# Sheet1.net
KiCad netlist of a schematic drawn in Altium Designer
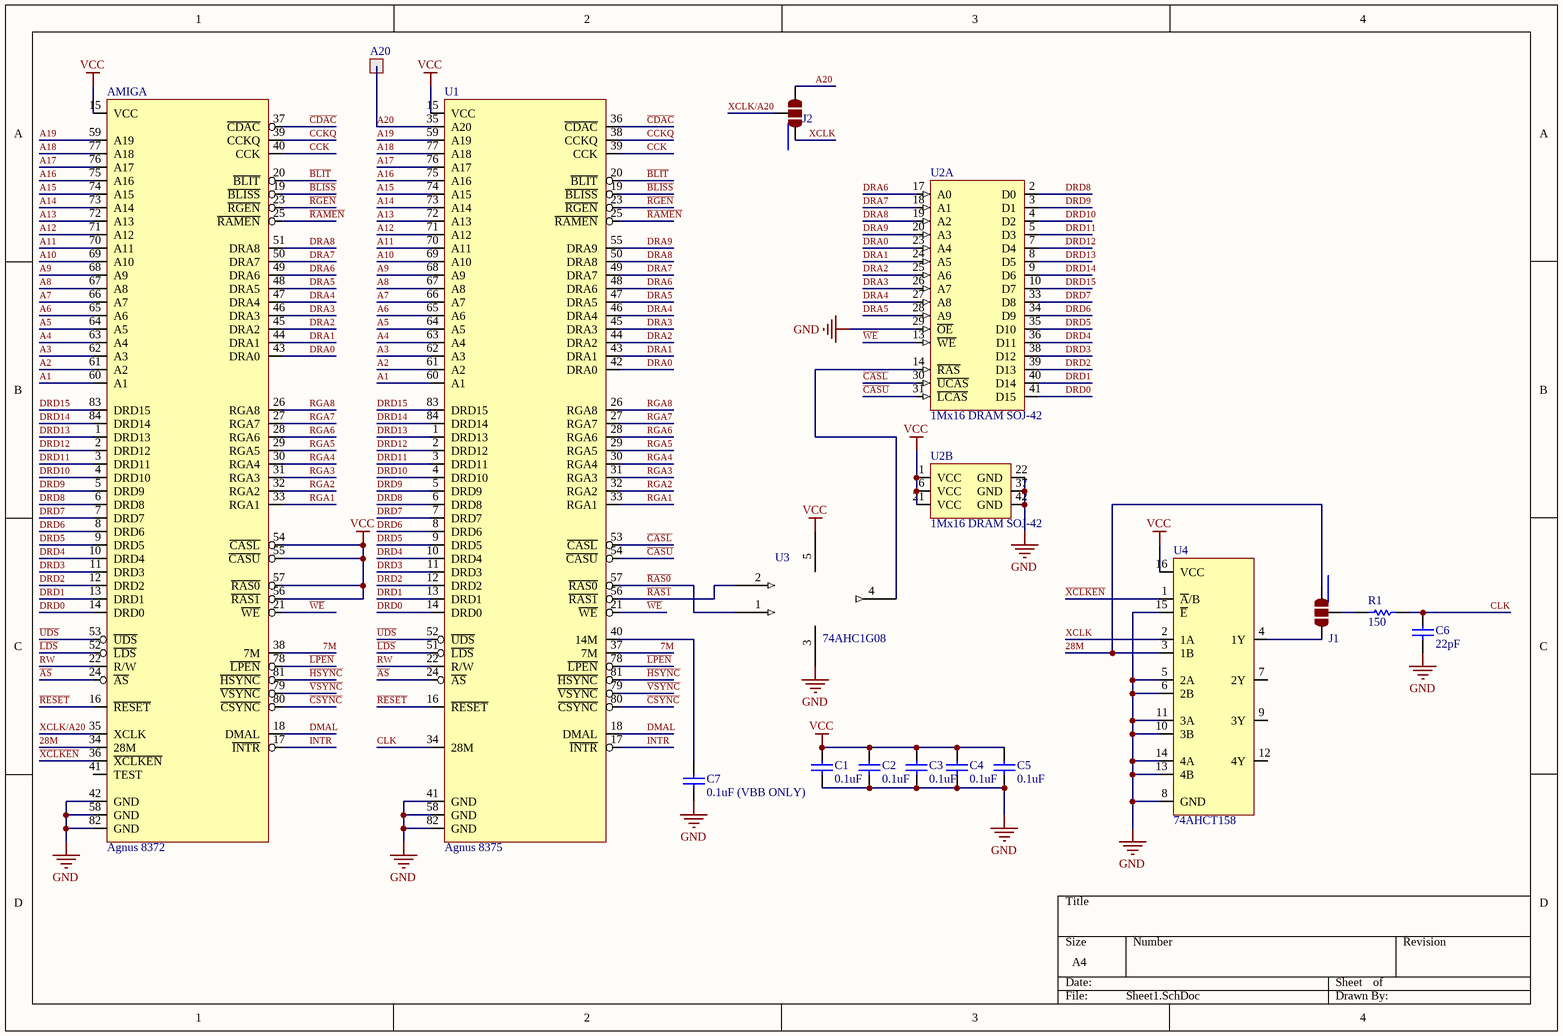
[diagram p0: Sheet1.SchDoc]

(export (version "E")
  (design (tool "Eeschema 10.0.6"))
  (components
    (comp (ref "A20")
      (value "Molex 90120-0761")
      (footprint "PCB-u1j2a009byds4mriae4x-1")
      (description "2.54mm (.100\") Pitch C-Grid III Header, Single Row, Vertical, 40 Circuits, Gold (Au) Plating")
      (fields (field (name "MANUFACTURER PART NUMBER") "90120-0761"))
      (libsource (lib "CommunityVault") (part "CMP-b48f7df16db76b48-3"))
    )
    (comp (ref "AMIGA")
      (value "Agnus 8372")
      (footprint "PLCC Male plug")
      (description "1MB Agnus (A500/2000)")
      (libsource (lib "CommunityVault") (part "CMP-efwu862vrdu0d84ikc4y-6"))
    )
    (comp (ref "C1")
      (value "0.1uF")
      (footprint "CAPC2013X94X50NL20T25")
      (description "CAP CER 0.1UF 25V Y5V 0805")
      (fields (field (name "MANUFACTURER PART NUMBER") "08053G104ZAT2A"))
      (libsource (lib "CommunityVault") (part "CMP-126070-2"))
    )
    (comp (ref "C2")
      (value "0.1uF")
      (footprint "CAPC2013X94X50NL20T25")
      (description "CAP CER 0.1UF 25V Y5V 0805")
      (fields (field (name "MANUFACTURER PART NUMBER") "08053G104ZAT2A"))
      (libsource (lib "CommunityVault") (part "CMP-126070-2"))
    )
    (comp (ref "C3")
      (value "0.1uF")
      (footprint "CAPC2013X94X50NL20T25")
      (description "CAP CER 0.1UF 25V Y5V 0805")
      (fields (field (name "MANUFACTURER PART NUMBER") "08053G104ZAT2A"))
      (libsource (lib "CommunityVault") (part "CMP-126070-2"))
    )
    (comp (ref "C4")
      (value "0.1uF")
      (footprint "CAPC2013X94X50NL20T25")
      (description "CAP CER 0.1UF 25V Y5V 0805")
      (fields (field (name "MANUFACTURER PART NUMBER") "08053G104ZAT2A"))
      (libsource (lib "CommunityVault") (part "CMP-126070-2"))
    )
    (comp (ref "C5")
      (value "0.1uF")
      (footprint "CAPC2013X94X50NL20T25")
      (description "CAP CER 0.1UF 25V Y5V 0805")
      (fields (field (name "MANUFACTURER PART NUMBER") "08053G104ZAT2A"))
      (libsource (lib "CommunityVault") (part "CMP-126070-2"))
    )
    (comp (ref "C6")
      (value "22pF")
      (footprint "CAPC2013X140X50NL20T25")
      (description "CAP CER 22PF 100V 5% NP0 0805")
      (fields (field (name "MANUFACTURER PART NUMBER") "08051A220J4T2A"))
      (libsource (lib "CommunityVault") (part "CMP-172484-2"))
    )
    (comp (ref "C7")
      (value "0.1uF (VBB ONLY)")
      (footprint "CAPC2013X94X50NL20T25")
      (description "CAP CER 0.1UF 25V Y5V 0805")
      (fields (field (name "MANUFACTURER PART NUMBER") "08053G104ZAT2A"))
      (libsource (lib "CommunityVault") (part "CMP-126070-2"))
    )
    (comp (ref "J1")
      (value "H1")
      (footprint "PCB-rrnqmtokqinrd1vbp5jt-1")
      (description "SMD Jumper")
      (libsource (lib "FavoritesLibrary") (part "SYM-0rfjo47dqw9gp5mzow1m-1"))
    )
    (comp (ref "J2")
      (value "H1")
      (footprint "PCB-rrnqmtokqinrd1vbp5jt-1")
      (description "SMD Jumper")
      (libsource (lib "CommunityVault") (part "CMP-0rfjo47dqw9gp5mzow1m-3"))
    )
    (comp (ref "R1")
      (value "150")
      (footprint "RESC2013X60X30NL20T20")
      (description "Res Thick Film 0805 150 Ohm 1% 1/8W ±100ppm/C Molded SMD SMD Punched Paper T/R")
      (fields (field (name "MANUFACTURER PART NUMBER") "RK73H2ATTD1500F"))
      (libsource (lib "CommunityVault") (part "CMP-2823328-2"))
    )
    (comp (ref "U1")
      (value "Agnus 8375")
      (footprint "PCBComponent_1")
      (description "2MB Agnus (A500+/A600)")
      (libsource (lib "CommunityVault") (part "CMP-7khi6ttu66jii6hcxoo5-4"))
    )
    (comp (ref "U2")
      (value "1Mx16 DRAM SOJ-42")
      (footprint "SOP42")
      (description "Generic 5V 16Mbit EDO DRAM SOJ42")
      (libsource (lib "CommunityVault") (part "CMP-upz9ayrn6n7gqqnzejzn-3"))
    )
    (comp (ref "U3")
      (value "74AHC1G08")
      (footprint "PCB-hs9ieo8jn20xo1glw5j0-1")
      (description "Logic, And Gate, Single, 2 i/p, Tssop-5")
      (libsource (lib "FavoritesLibrary") (part "SYM-eb1b2368527234dc-1"))
    )
    (comp (ref "U4")
      (value "74AHCT158")
      (footprint "PCB-c1qa6rkk0qsamo5yebiy-1")
      (description "74AHC Series 2 to 5.5 V Quad 2-Input Multiplexer Surface Mount - SOIC-16")
      (fields (field (name "MANUFACTURER PART NUMBER") "74AHC157D,112"))
      (libsource (lib "CommunityVault") (part "CMP-483e8585f23297f9-2"))
    )
  )
  (nets
    (net (code "1") (name "/7M") (class "Default")
      (node (ref "AMIGA") (pin "38") (pinfunction "7M_38") (pintype "passive"))
      (node (ref "U1") (pin "37") (pinfunction "7M_37") (pintype "passive"))
    )
    (net (code "2") (name "/28M") (class "Default")
      (node (ref "AMIGA") (pin "34") (pinfunction "28M_34") (pintype "passive"))
      (node (ref "J1") (pin "1") (pinfunction "1_1") (pintype "passive"))
      (node (ref "U4") (pin "3") (pinfunction "1B_3") (pintype "passive"))
    )
    (net (code "3") (name "/A1") (class "Default")
      (node (ref "AMIGA") (pin "60") (pinfunction "A1_60") (pintype "passive"))
      (node (ref "U1") (pin "60") (pinfunction "A1_60") (pintype "passive"))
    )
    (net (code "4") (name "/A2") (class "Default")
      (node (ref "AMIGA") (pin "61") (pinfunction "A2_61") (pintype "passive"))
      (node (ref "U1") (pin "61") (pinfunction "A2_61") (pintype "passive"))
    )
    (net (code "5") (name "/A3") (class "Default")
      (node (ref "AMIGA") (pin "62") (pinfunction "A3_62") (pintype "passive"))
      (node (ref "U1") (pin "62") (pinfunction "A3_62") (pintype "passive"))
    )
    (net (code "6") (name "/A4") (class "Default")
      (node (ref "AMIGA") (pin "63") (pinfunction "A4_63") (pintype "passive"))
      (node (ref "U1") (pin "63") (pinfunction "A4_63") (pintype "passive"))
    )
    (net (code "7") (name "/A5") (class "Default")
      (node (ref "AMIGA") (pin "64") (pinfunction "A5_64") (pintype "passive"))
      (node (ref "U1") (pin "64") (pinfunction "A5_64") (pintype "passive"))
    )
    (net (code "8") (name "/A6") (class "Default")
      (node (ref "AMIGA") (pin "65") (pinfunction "A6_65") (pintype "passive"))
      (node (ref "U1") (pin "65") (pinfunction "A6_65") (pintype "passive"))
    )
    (net (code "9") (name "/A7") (class "Default")
      (node (ref "AMIGA") (pin "66") (pinfunction "A7_66") (pintype "passive"))
      (node (ref "U1") (pin "66") (pinfunction "A7_66") (pintype "passive"))
    )
    (net (code "10") (name "/A8") (class "Default")
      (node (ref "AMIGA") (pin "67") (pinfunction "A8_67") (pintype "passive"))
      (node (ref "U1") (pin "67") (pinfunction "A8_67") (pintype "passive"))
    )
    (net (code "11") (name "/A9") (class "Default")
      (node (ref "AMIGA") (pin "68") (pinfunction "A9_68") (pintype "passive"))
      (node (ref "U1") (pin "68") (pinfunction "A9_68") (pintype "passive"))
    )
    (net (code "12") (name "/A10") (class "Default")
      (node (ref "AMIGA") (pin "69") (pinfunction "A10_69") (pintype "passive"))
      (node (ref "U1") (pin "69") (pinfunction "A10_69") (pintype "passive"))
    )
    (net (code "13") (name "/A11") (class "Default")
      (node (ref "AMIGA") (pin "70") (pinfunction "A11_70") (pintype "passive"))
      (node (ref "U1") (pin "70") (pinfunction "A11_70") (pintype "passive"))
    )
    (net (code "14") (name "/A12") (class "Default")
      (node (ref "AMIGA") (pin "71") (pinfunction "A12_71") (pintype "passive"))
      (node (ref "U1") (pin "71") (pinfunction "A12_71") (pintype "passive"))
    )
    (net (code "15") (name "/A13") (class "Default")
      (node (ref "AMIGA") (pin "72") (pinfunction "A13_72") (pintype "passive"))
      (node (ref "U1") (pin "72") (pinfunction "A13_72") (pintype "passive"))
    )
    (net (code "16") (name "/A14") (class "Default")
      (node (ref "AMIGA") (pin "73") (pinfunction "A14_73") (pintype "passive"))
      (node (ref "U1") (pin "73") (pinfunction "A14_73") (pintype "passive"))
    )
    (net (code "17") (name "/A15") (class "Default")
      (node (ref "AMIGA") (pin "74") (pinfunction "A15_74") (pintype "passive"))
      (node (ref "U1") (pin "74") (pinfunction "A15_74") (pintype "passive"))
    )
    (net (code "18") (name "/A16") (class "Default")
      (node (ref "AMIGA") (pin "75") (pinfunction "A16_75") (pintype "passive"))
      (node (ref "U1") (pin "75") (pinfunction "A16_75") (pintype "passive"))
    )
    (net (code "19") (name "/A17") (class "Default")
      (node (ref "AMIGA") (pin "76") (pinfunction "A17_76") (pintype "passive"))
      (node (ref "U1") (pin "76") (pinfunction "A17_76") (pintype "passive"))
    )
    (net (code "20") (name "/A18") (class "Default")
      (node (ref "AMIGA") (pin "77") (pinfunction "A18_77") (pintype "passive"))
      (node (ref "U1") (pin "77") (pinfunction "A18_77") (pintype "passive"))
    )
    (net (code "21") (name "/A19") (class "Default")
      (node (ref "AMIGA") (pin "59") (pinfunction "A19_59") (pintype "passive"))
      (node (ref "U1") (pin "59") (pinfunction "A19_59") (pintype "passive"))
    )
    (net (code "22") (name "/A20") (class "Default")
      (node (ref "A20") (pin "1") (pinfunction "1_1") (pintype "passive"))
      (node (ref "J2") (pin "3") (pinfunction "3_3") (pintype "passive"))
      (node (ref "U1") (pin "35") (pinfunction "A20_35") (pintype "passive"))
    )
    (net (code "23") (name "/CCK") (class "Default")
      (node (ref "AMIGA") (pin "40") (pinfunction "CCK_40") (pintype "passive"))
      (node (ref "U1") (pin "39") (pinfunction "CCK_39") (pintype "passive"))
    )
    (net (code "24") (name "/CCKQ") (class "Default")
      (node (ref "AMIGA") (pin "39") (pinfunction "CCKQ_39") (pintype "passive"))
      (node (ref "U1") (pin "38") (pinfunction "CCKQ_38") (pintype "passive"))
    )
    (net (code "25") (name "/CLK") (class "Default")
      (node (ref "C6") (pin "2") (pinfunction "2_2") (pintype "passive"))
      (node (ref "R1") (pin "2") (pinfunction "2_2") (pintype "passive"))
      (node (ref "U1") (pin "34") (pinfunction "28M_34") (pintype "passive"))
    )
    (net (code "26") (name "/DMAL") (class "Default")
      (node (ref "AMIGA") (pin "18") (pinfunction "DMAL_18") (pintype "passive"))
      (node (ref "U1") (pin "18") (pinfunction "DMAL_18") (pintype "passive"))
    )
    (net (code "27") (name "/DRA0") (class "Default")
      (node (ref "AMIGA") (pin "43") (pinfunction "DRA0_43") (pintype "passive"))
      (node (ref "U1") (pin "42") (pinfunction "DRA0_42") (pintype "passive"))
      (node (ref "U2") (pin "23") (pinfunction "A4_23") (pintype "input"))
    )
    (net (code "28") (name "/DRA1") (class "Default")
      (node (ref "AMIGA") (pin "44") (pinfunction "DRA1_44") (pintype "passive"))
      (node (ref "U1") (pin "43") (pinfunction "DRA1_43") (pintype "passive"))
      (node (ref "U2") (pin "24") (pinfunction "A5_24") (pintype "input"))
    )
    (net (code "29") (name "/DRA2") (class "Default")
      (node (ref "AMIGA") (pin "45") (pinfunction "DRA2_45") (pintype "passive"))
      (node (ref "U1") (pin "44") (pinfunction "DRA2_44") (pintype "passive"))
      (node (ref "U2") (pin "25") (pinfunction "A6_25") (pintype "input"))
    )
    (net (code "30") (name "/DRA3") (class "Default")
      (node (ref "AMIGA") (pin "46") (pinfunction "DRA3_46") (pintype "passive"))
      (node (ref "U1") (pin "45") (pinfunction "DRA3_45") (pintype "passive"))
      (node (ref "U2") (pin "26") (pinfunction "A7_26") (pintype "input"))
    )
    (net (code "31") (name "/DRA4") (class "Default")
      (node (ref "AMIGA") (pin "47") (pinfunction "DRA4_47") (pintype "passive"))
      (node (ref "U1") (pin "46") (pinfunction "DRA4_46") (pintype "passive"))
      (node (ref "U2") (pin "27") (pinfunction "A8_27") (pintype "input"))
    )
    (net (code "32") (name "/DRA5") (class "Default")
      (node (ref "AMIGA") (pin "48") (pinfunction "DRA5_48") (pintype "passive"))
      (node (ref "U1") (pin "47") (pinfunction "DRA5_47") (pintype "passive"))
      (node (ref "U2") (pin "28") (pinfunction "A9_28") (pintype "input"))
    )
    (net (code "33") (name "/DRA6") (class "Default")
      (node (ref "AMIGA") (pin "49") (pinfunction "DRA6_49") (pintype "passive"))
      (node (ref "U1") (pin "48") (pinfunction "DRA6_48") (pintype "passive"))
      (node (ref "U2") (pin "17") (pinfunction "A0_17") (pintype "input"))
    )
    (net (code "34") (name "/DRA7") (class "Default")
      (node (ref "AMIGA") (pin "50") (pinfunction "DRA7_50") (pintype "passive"))
      (node (ref "U1") (pin "49") (pinfunction "DRA7_49") (pintype "passive"))
      (node (ref "U2") (pin "18") (pinfunction "A1_18") (pintype "input"))
    )
    (net (code "35") (name "/DRA8") (class "Default")
      (node (ref "AMIGA") (pin "51") (pinfunction "DRA8_51") (pintype "passive"))
      (node (ref "U1") (pin "50") (pinfunction "DRA8_50") (pintype "passive"))
      (node (ref "U2") (pin "19") (pinfunction "A2_19") (pintype "input"))
    )
    (net (code "36") (name "/DRA9") (class "Default")
      (node (ref "U1") (pin "55") (pinfunction "DRA9_55") (pintype "passive"))
      (node (ref "U2") (pin "20") (pinfunction "A3_20") (pintype "input"))
    )
    (net (code "37") (name "/DRD0") (class "Default")
      (node (ref "AMIGA") (pin "14") (pinfunction "DRD0_14") (pintype "passive"))
      (node (ref "U1") (pin "14") (pinfunction "DRD0_14") (pintype "passive"))
      (node (ref "U2") (pin "41") (pinfunction "D15_41") (pintype "bidirectional"))
    )
    (net (code "38") (name "/DRD1") (class "Default")
      (node (ref "AMIGA") (pin "13") (pinfunction "DRD1_13") (pintype "passive"))
      (node (ref "U1") (pin "13") (pinfunction "DRD1_13") (pintype "passive"))
      (node (ref "U2") (pin "40") (pinfunction "D14_40") (pintype "bidirectional"))
    )
    (net (code "39") (name "/DRD2") (class "Default")
      (node (ref "AMIGA") (pin "12") (pinfunction "DRD2_12") (pintype "passive"))
      (node (ref "U1") (pin "12") (pinfunction "DRD2_12") (pintype "passive"))
      (node (ref "U2") (pin "39") (pinfunction "D13_39") (pintype "bidirectional"))
    )
    (net (code "40") (name "/DRD3") (class "Default")
      (node (ref "AMIGA") (pin "11") (pinfunction "DRD3_11") (pintype "passive"))
      (node (ref "U1") (pin "11") (pinfunction "DRD3_11") (pintype "passive"))
      (node (ref "U2") (pin "38") (pinfunction "D12_38") (pintype "bidirectional"))
    )
    (net (code "41") (name "/DRD4") (class "Default")
      (node (ref "AMIGA") (pin "10") (pinfunction "DRD4_10") (pintype "passive"))
      (node (ref "U1") (pin "10") (pinfunction "DRD4_10") (pintype "passive"))
      (node (ref "U2") (pin "36") (pinfunction "D11_36") (pintype "bidirectional"))
    )
    (net (code "42") (name "/DRD5") (class "Default")
      (node (ref "AMIGA") (pin "9") (pinfunction "DRD5_9") (pintype "passive"))
      (node (ref "U1") (pin "9") (pinfunction "DRD5_9") (pintype "passive"))
      (node (ref "U2") (pin "35") (pinfunction "D10_35") (pintype "bidirectional"))
    )
    (net (code "43") (name "/DRD6") (class "Default")
      (node (ref "AMIGA") (pin "8") (pinfunction "DRD6_8") (pintype "passive"))
      (node (ref "U1") (pin "8") (pinfunction "DRD6_8") (pintype "passive"))
      (node (ref "U2") (pin "34") (pinfunction "D9_34") (pintype "bidirectional"))
    )
    (net (code "44") (name "/DRD7") (class "Default")
      (node (ref "AMIGA") (pin "7") (pinfunction "DRD7_7") (pintype "passive"))
      (node (ref "U1") (pin "7") (pinfunction "DRD7_7") (pintype "passive"))
      (node (ref "U2") (pin "33") (pinfunction "D8_33") (pintype "bidirectional"))
    )
    (net (code "45") (name "/DRD8") (class "Default")
      (node (ref "AMIGA") (pin "6") (pinfunction "DRD8_6") (pintype "passive"))
      (node (ref "U1") (pin "6") (pinfunction "DRD8_6") (pintype "passive"))
      (node (ref "U2") (pin "2") (pinfunction "D0_2") (pintype "bidirectional"))
    )
    (net (code "46") (name "/DRD9") (class "Default")
      (node (ref "AMIGA") (pin "5") (pinfunction "DRD9_5") (pintype "passive"))
      (node (ref "U1") (pin "5") (pinfunction "DRD9_5") (pintype "passive"))
      (node (ref "U2") (pin "3") (pinfunction "D1_3") (pintype "bidirectional"))
    )
    (net (code "47") (name "/DRD10") (class "Default")
      (node (ref "AMIGA") (pin "4") (pinfunction "DRD10_4") (pintype "passive"))
      (node (ref "U1") (pin "4") (pinfunction "DRD10_4") (pintype "passive"))
      (node (ref "U2") (pin "4") (pinfunction "D2_4") (pintype "bidirectional"))
    )
    (net (code "48") (name "/DRD11") (class "Default")
      (node (ref "AMIGA") (pin "3") (pinfunction "DRD11_3") (pintype "passive"))
      (node (ref "U1") (pin "3") (pinfunction "DRD11_3") (pintype "passive"))
      (node (ref "U2") (pin "5") (pinfunction "D3_5") (pintype "bidirectional"))
    )
    (net (code "49") (name "/DRD12") (class "Default")
      (node (ref "AMIGA") (pin "2") (pinfunction "DRD12_2") (pintype "passive"))
      (node (ref "U1") (pin "2") (pinfunction "DRD12_2") (pintype "passive"))
      (node (ref "U2") (pin "7") (pinfunction "D4_7") (pintype "bidirectional"))
    )
    (net (code "50") (name "/DRD13") (class "Default")
      (node (ref "AMIGA") (pin "1") (pinfunction "DRD13_1") (pintype "passive"))
      (node (ref "U1") (pin "1") (pinfunction "DRD13_1") (pintype "passive"))
      (node (ref "U2") (pin "8") (pinfunction "D5_8") (pintype "bidirectional"))
    )
    (net (code "51") (name "/DRD14") (class "Default")
      (node (ref "AMIGA") (pin "84") (pinfunction "DRD14_84") (pintype "passive"))
      (node (ref "U1") (pin "84") (pinfunction "DRD14_84") (pintype "passive"))
      (node (ref "U2") (pin "9") (pinfunction "D6_9") (pintype "bidirectional"))
    )
    (net (code "52") (name "/DRD15") (class "Default")
      (node (ref "AMIGA") (pin "83") (pinfunction "DRD15_83") (pintype "passive"))
      (node (ref "U1") (pin "83") (pinfunction "DRD15_83") (pintype "passive"))
      (node (ref "U2") (pin "10") (pinfunction "D7_10") (pintype "bidirectional"))
    )
    (net (code "53") (name "/INTR") (class "Default")
      (node (ref "AMIGA") (pin "17") (pinfunction "~{INTR}_17") (pintype "passive"))
      (node (ref "U1") (pin "17") (pinfunction "~{INTR}_17") (pintype "passive"))
    )
    (net (code "54") (name "/RGA1") (class "Default")
      (node (ref "AMIGA") (pin "33") (pinfunction "RGA1_33") (pintype "passive"))
      (node (ref "U1") (pin "33") (pinfunction "RGA1_33") (pintype "passive"))
    )
    (net (code "55") (name "/RGA2") (class "Default")
      (node (ref "AMIGA") (pin "32") (pinfunction "RGA2_32") (pintype "passive"))
      (node (ref "U1") (pin "32") (pinfunction "RGA2_32") (pintype "passive"))
    )
    (net (code "56") (name "/RGA3") (class "Default")
      (node (ref "AMIGA") (pin "31") (pinfunction "RGA3_31") (pintype "passive"))
      (node (ref "U1") (pin "31") (pinfunction "RGA3_31") (pintype "passive"))
    )
    (net (code "57") (name "/RGA4") (class "Default")
      (node (ref "AMIGA") (pin "30") (pinfunction "RGA4_30") (pintype "passive"))
      (node (ref "U1") (pin "30") (pinfunction "RGA4_30") (pintype "passive"))
    )
    (net (code "58") (name "/RGA5") (class "Default")
      (node (ref "AMIGA") (pin "29") (pinfunction "RGA5_29") (pintype "passive"))
      (node (ref "U1") (pin "29") (pinfunction "RGA5_29") (pintype "passive"))
    )
    (net (code "59") (name "/RGA6") (class "Default")
      (node (ref "AMIGA") (pin "28") (pinfunction "RGA6_28") (pintype "passive"))
      (node (ref "U1") (pin "28") (pinfunction "RGA6_28") (pintype "passive"))
    )
    (net (code "60") (name "/RGA7") (class "Default")
      (node (ref "AMIGA") (pin "27") (pinfunction "RGA7_27") (pintype "passive"))
      (node (ref "U1") (pin "27") (pinfunction "RGA7_27") (pintype "passive"))
    )
    (net (code "61") (name "/RGA8") (class "Default")
      (node (ref "AMIGA") (pin "26") (pinfunction "RGA8_26") (pintype "passive"))
      (node (ref "U1") (pin "26") (pinfunction "RGA8_26") (pintype "passive"))
    )
    (net (code "62") (name "/RW") (class "Default")
      (node (ref "AMIGA") (pin "22") (pinfunction "R/W_22") (pintype "power_in"))
      (node (ref "U1") (pin "22") (pinfunction "R/W_22") (pintype "power_in"))
    )
    (net (code "63") (name "/XCLK") (class "Default")
      (node (ref "J2") (pin "1") (pinfunction "1_1") (pintype "passive"))
      (node (ref "U4") (pin "2") (pinfunction "1A_2") (pintype "passive"))
    )
    (net (code "64") (name "/XCLK{slash}A20") (class "Default")
      (node (ref "AMIGA") (pin "35") (pinfunction "XCLK_35") (pintype "passive"))
      (node (ref "J2") (pin "2") (pinfunction "2_2") (pintype "passive"))
    )
    (net (code "65") (name "/~{AS}") (class "Default")
      (node (ref "AMIGA") (pin "24") (pinfunction "~{AS}_24") (pintype "passive"))
      (node (ref "U1") (pin "24") (pinfunction "~{AS}_24") (pintype "passive"))
    )
    (net (code "66") (name "/~{BLISS}") (class "Default")
      (node (ref "AMIGA") (pin "19") (pinfunction "~{BLISS}_19") (pintype "passive"))
      (node (ref "U1") (pin "19") (pinfunction "~{BLISS}_19") (pintype "passive"))
    )
    (net (code "67") (name "/~{BLIT}") (class "Default")
      (node (ref "AMIGA") (pin "20") (pinfunction "~{BLIT}_20") (pintype "passive"))
      (node (ref "U1") (pin "20") (pinfunction "~{BLIT}_20") (pintype "passive"))
    )
    (net (code "68") (name "/~{CASL}") (class "Default")
      (node (ref "U1") (pin "53") (pinfunction "~{CASL}_53") (pintype "passive"))
      (node (ref "U2") (pin "30") (pinfunction "~{UCAS}_30") (pintype "input"))
    )
    (net (code "69") (name "/~{CASU}") (class "Default")
      (node (ref "U1") (pin "54") (pinfunction "~{CASU}_54") (pintype "passive"))
      (node (ref "U2") (pin "31") (pinfunction "~{LCAS}_31") (pintype "input"))
    )
    (net (code "70") (name "/~{CDAC}") (class "Default")
      (node (ref "AMIGA") (pin "37") (pinfunction "~{CDAC}_37") (pintype "passive"))
      (node (ref "U1") (pin "36") (pinfunction "~{CDAC}_36") (pintype "passive"))
    )
    (net (code "71") (name "/~{CSYNC}") (class "Default")
      (node (ref "AMIGA") (pin "80") (pinfunction "~{CSYNC}_80") (pintype "passive"))
      (node (ref "U1") (pin "80") (pinfunction "~{CSYNC}_80") (pintype "passive"))
    )
    (net (code "72") (name "/~{HSYNC}") (class "Default")
      (node (ref "AMIGA") (pin "81") (pinfunction "~{HSYNC}_81") (pintype "passive"))
      (node (ref "U1") (pin "81") (pinfunction "~{HSYNC}_81") (pintype "passive"))
    )
    (net (code "73") (name "/~{LDS}") (class "Default")
      (node (ref "AMIGA") (pin "52") (pinfunction "~{LDS}_52") (pintype "open_collector"))
      (node (ref "U1") (pin "51") (pinfunction "~{LDS}_51") (pintype "passive"))
    )
    (net (code "74") (name "/~{LPEN}") (class "Default")
      (node (ref "AMIGA") (pin "78") (pinfunction "~{LPEN}_78") (pintype "passive"))
      (node (ref "U1") (pin "78") (pinfunction "~{LPEN}_78") (pintype "passive"))
    )
    (net (code "75") (name "/~{RAMEN}") (class "Default")
      (node (ref "AMIGA") (pin "25") (pinfunction "~{RAMEN}_25") (pintype "passive"))
      (node (ref "U1") (pin "25") (pinfunction "~{RAMEN}_25") (pintype "passive"))
    )
    (net (code "76") (name "/~{RAS0}") (class "Default")
      (node (ref "U1") (pin "57") (pinfunction "~{RAS0}_57") (pintype "passive"))
      (node (ref "U3") (pin "1") (pinfunction "B_1") (pintype "input"))
    )
    (net (code "77") (name "/~{RAS1}") (class "Default")
      (node (ref "U1") (pin "56") (pinfunction "~{RAS1}_56") (pintype "passive"))
      (node (ref "U3") (pin "2") (pinfunction "A_2") (pintype "input"))
    )
    (net (code "78") (name "/~{RESET}") (class "Default")
      (node (ref "AMIGA") (pin "16") (pinfunction "~{RESET}_16") (pintype "passive"))
      (node (ref "U1") (pin "16") (pinfunction "~{RESET}_16") (pintype "passive"))
    )
    (net (code "79") (name "/~{RGEN}") (class "Default")
      (node (ref "AMIGA") (pin "23") (pinfunction "~{RGEN}_23") (pintype "passive"))
      (node (ref "U1") (pin "23") (pinfunction "~{RGEN}_23") (pintype "passive"))
    )
    (net (code "80") (name "/~{UDS}") (class "Default")
      (node (ref "AMIGA") (pin "53") (pinfunction "~{UDS}_53") (pintype "passive"))
      (node (ref "U1") (pin "52") (pinfunction "~{UDS}_52") (pintype "open_collector"))
    )
    (net (code "81") (name "/~{VSYNC}") (class "Default")
      (node (ref "AMIGA") (pin "79") (pinfunction "~{VSYNC}_79") (pintype "passive"))
      (node (ref "U1") (pin "79") (pinfunction "~{VSYNC}_79") (pintype "passive"))
    )
    (net (code "82") (name "/~{WE}") (class "Default")
      (node (ref "AMIGA") (pin "21") (pinfunction "~{WE}_21") (pintype "passive"))
      (node (ref "U1") (pin "21") (pinfunction "~{WE}_21") (pintype "passive"))
      (node (ref "U2") (pin "13") (pinfunction "~{WE}_13") (pintype "input"))
    )
    (net (code "83") (name "/~{XCLKEN}") (class "Default")
      (node (ref "AMIGA") (pin "36") (pinfunction "~{XCLKEN}_36") (pintype "passive"))
      (node (ref "U4") (pin "1") (pinfunction "~{A}/B_1") (pintype "passive"))
    )
    (net (code "84") (name "GND") (class "Default")
      (node (ref "AMIGA") (pin "42") (pinfunction "GND_42") (pintype "power_in"))
      (node (ref "AMIGA") (pin "58") (pinfunction "GND_58") (pintype "power_in"))
      (node (ref "AMIGA") (pin "82") (pinfunction "GND_82") (pintype "power_in"))
      (node (ref "C1") (pin "1") (pinfunction "1_1") (pintype "passive"))
      (node (ref "C2") (pin "1") (pinfunction "1_1") (pintype "passive"))
      (node (ref "C3") (pin "1") (pinfunction "1_1") (pintype "passive"))
      (node (ref "C4") (pin "1") (pinfunction "1_1") (pintype "passive"))
      (node (ref "C5") (pin "1") (pinfunction "1_1") (pintype "passive"))
      (node (ref "C6") (pin "1") (pinfunction "1_1") (pintype "passive"))
      (node (ref "C7") (pin "1") (pinfunction "1_1") (pintype "passive"))
      (node (ref "U1") (pin "41") (pinfunction "GND_41") (pintype "passive"))
      (node (ref "U1") (pin "58") (pinfunction "GND_58") (pintype "power_in"))
      (node (ref "U1") (pin "82") (pinfunction "GND_82") (pintype "power_in"))
      (node (ref "U2") (pin "22") (pinfunction "GND_22") (pintype "power_in"))
      (node (ref "U2") (pin "29") (pinfunction "~{OE}_29") (pintype "input"))
      (node (ref "U2") (pin "37") (pinfunction "GND_37") (pintype "power_in"))
      (node (ref "U2") (pin "42") (pinfunction "GND_42") (pintype "power_in"))
      (node (ref "U3") (pin "3") (pinfunction "GND_3") (pintype "power_in"))
      (node (ref "U4") (pin "10") (pinfunction "3B_10") (pintype "passive"))
      (node (ref "U4") (pin "11") (pinfunction "3A_11") (pintype "passive"))
      (node (ref "U4") (pin "13") (pinfunction "4B_13") (pintype "passive"))
      (node (ref "U4") (pin "14") (pinfunction "4A_14") (pintype "passive"))
      (node (ref "U4") (pin "15") (pinfunction "~{E}_15") (pintype "passive"))
      (node (ref "U4") (pin "5") (pinfunction "2A_5") (pintype "passive"))
      (node (ref "U4") (pin "6") (pinfunction "2B_6") (pintype "passive"))
      (node (ref "U4") (pin "8") (pinfunction "GND_8") (pintype "power_in"))
    )
    (net (code "85") (name "Net-(J1-Pad2)") (class "Default")
      (node (ref "J1") (pin "2") (pinfunction "2_2") (pintype "passive"))
      (node (ref "R1") (pin "1") (pinfunction "1_1") (pintype "passive"))
    )
    (net (code "86") (name "Net-(U1-14M)") (class "Default")
      (node (ref "C7") (pin "2") (pinfunction "2_2") (pintype "passive"))
      (node (ref "U1") (pin "40") (pinfunction "14M_40") (pintype "passive"))
    )
    (net (code "87") (name "Net-(U2A-~{RAS})") (class "Default")
      (node (ref "U2") (pin "14") (pinfunction "~{RAS}_14") (pintype "input"))
      (node (ref "U3") (pin "4") (pinfunction "Y_4") (pintype "output"))
    )
    (net (code "88") (name "Net-(U4-1Y)") (class "Default")
      (node (ref "J1") (pin "3") (pinfunction "3_3") (pintype "passive"))
      (node (ref "U4") (pin "4") (pinfunction "1Y_4") (pintype "passive"))
    )
    (net (code "89") (name "VCC") (class "Default")
      (node (ref "AMIGA") (pin "15") (pinfunction "VCC_15") (pintype "power_in"))
      (node (ref "AMIGA") (pin "54") (pinfunction "~{CASL}_54") (pintype "passive"))
      (node (ref "AMIGA") (pin "55") (pinfunction "~{CASU}_55") (pintype "passive"))
      (node (ref "AMIGA") (pin "56") (pinfunction "~{RAS1}_56") (pintype "passive"))
      (node (ref "AMIGA") (pin "57") (pinfunction "~{RAS0}_57") (pintype "passive"))
      (node (ref "C1") (pin "2") (pinfunction "2_2") (pintype "passive"))
      (node (ref "C2") (pin "2") (pinfunction "2_2") (pintype "passive"))
      (node (ref "C3") (pin "2") (pinfunction "2_2") (pintype "passive"))
      (node (ref "C4") (pin "2") (pinfunction "2_2") (pintype "passive"))
      (node (ref "C5") (pin "2") (pinfunction "2_2") (pintype "passive"))
      (node (ref "U1") (pin "15") (pinfunction "VCC_15") (pintype "power_in"))
      (node (ref "U2") (pin "1") (pinfunction "VCC_1") (pintype "power_in"))
      (node (ref "U2") (pin "21") (pinfunction "VCC_21") (pintype "power_in"))
      (node (ref "U2") (pin "6") (pinfunction "VCC_6") (pintype "power_in"))
      (node (ref "U3") (pin "5") (pinfunction "VCC_5") (pintype "power_in"))
      (node (ref "U4") (pin "16") (pinfunction "VCC_16") (pintype "power_in"))
    )
    (net (code "90") (name "unconnected-(AMIGA-TEST-Pad41)") (class "Default")
      (node (ref "AMIGA") (pin "41") (pinfunction "TEST_41") (pintype "passive"))
    )
    (net (code "91") (name "unconnected-(U4-2Y-Pad7)") (class "Default")
      (node (ref "U4") (pin "7") (pinfunction "2Y_7") (pintype "passive"))
    )
    (net (code "92") (name "unconnected-(U4-3Y-Pad9)") (class "Default")
      (node (ref "U4") (pin "9") (pinfunction "3Y_9") (pintype "passive"))
    )
    (net (code "93") (name "unconnected-(U4-4Y-Pad12)") (class "Default")
      (node (ref "U4") (pin "12") (pinfunction "4Y_12") (pintype "passive"))
    )
  )
)
